# Sensing.net
KiCad netlist of a schematic drawn in EAGLE
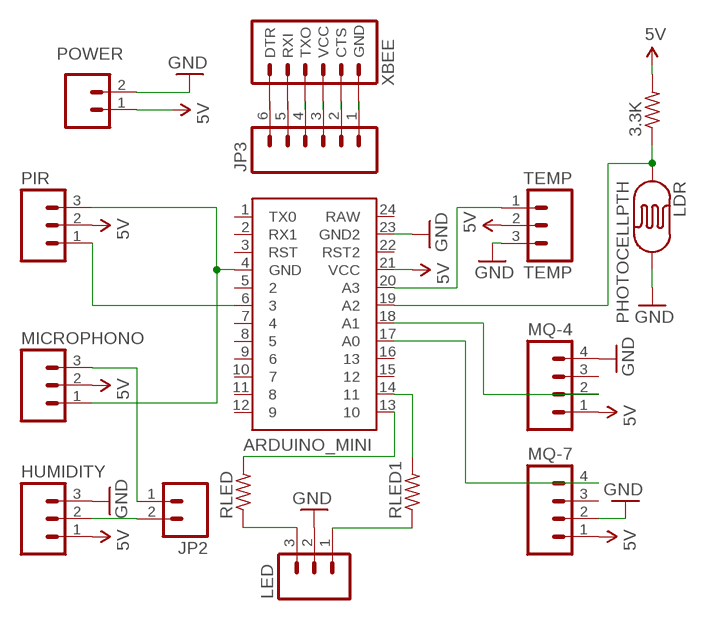
[diagram p0: schematic, sheet 1]

(export (version "E")
  (design (tool "Eeschema 10.0.6"))
  (components
    (comp (ref "3.3K")
      (value "R-US_M0805")
      (footprint "eagle-import:M0805")
      (libsource (lib "eagle-import") (part "R-US_M0805"))
    )
    (comp (ref "ARDUINO_MINI")
      (value "ARDUINO_MINI")
      (footprint "eagle-import:ARDUINO_MINI")
      (libsource (lib "eagle-import") (part "ARDUINO_MINI"))
    )
    (comp (ref "HUMIDITY")
      (value "HUMIDITY")
      (footprint "eagle-import:1X03")
      (libsource (lib "eagle-import") (part "M03PTH"))
    )
    (comp (ref "JP2")
      (value "M02PTH")
      (footprint "eagle-import:1X02")
      (libsource (lib "eagle-import") (part "M02PTH"))
    )
    (comp (ref "JP3")
      (value "M06SIP")
      (footprint "eagle-import:1X06")
      (libsource (lib "eagle-import") (part "M06SIP"))
    )
    (comp (ref "LDR")
      (value "PHOTOCELLPTH")
      (footprint "eagle-import:PHOTOCELL")
      (libsource (lib "eagle-import") (part "PHOTOCELLPTH"))
    )
    (comp (ref "LED")
      (value "M03PTH")
      (footprint "eagle-import:1X03")
      (libsource (lib "eagle-import") (part "M03PTH"))
    )
    (comp (ref "MICROPHONO")
      (value "M03PTH")
      (footprint "eagle-import:1X03")
      (libsource (lib "eagle-import") (part "M03PTH"))
    )
    (comp (ref "MQ-4")
      (value "M04PTH")
      (footprint "eagle-import:1X04")
      (libsource (lib "eagle-import") (part "M04PTH"))
    )
    (comp (ref "MQ-7")
      (value "M04PTH")
      (footprint "eagle-import:1X04")
      (libsource (lib "eagle-import") (part "M04PTH"))
    )
    (comp (ref "PIR")
      (value "M03PTH")
      (footprint "eagle-import:1X03")
      (libsource (lib "eagle-import") (part "M03PTH"))
    )
    (comp (ref "POWER")
      (value "M025MM")
      (footprint "eagle-import:SCREWTERMINAL-5MM-2")
      (libsource (lib "eagle-import") (part "M025MM"))
    )
    (comp (ref "RLED")
      (value "R-US_M0805")
      (footprint "eagle-import:M0805")
      (libsource (lib "eagle-import") (part "R-US_M0805"))
    )
    (comp (ref "RLED1")
      (value "R-US_M0805")
      (footprint "eagle-import:M0805")
      (libsource (lib "eagle-import") (part "R-US_M0805"))
    )
    (comp (ref "TEMP")
      (value "TEMP")
      (footprint "eagle-import:1X03_NO_SILK")
      (libsource (lib "eagle-import") (part "M031X03_NO_SILK"))
    )
    (comp (ref "XBEE")
      (value "ARDUINO_SERIAL_PROGRAMPTH")
      (footprint "eagle-import:1X06")
      (libsource (lib "eagle-import") (part "ARDUINO_SERIAL_PROGRAMPTH"))
    )
  )
  (nets
    (net (code "1") (name "5V") (class "Default")
      (node (ref "3.3K") (pin "2") (pinfunction "2_2") (pintype "passive"))
      (node (ref "ARDUINO_MINI") (pin "21") (pinfunction "VCC_21") (pintype "bidirectional"))
      (node (ref "HUMIDITY") (pin "1") (pinfunction "1_1") (pintype "passive"))
      (node (ref "MICROPHONO") (pin "2") (pinfunction "2_2") (pintype "passive"))
      (node (ref "MQ-4") (pin "1") (pinfunction "1_1") (pintype "passive"))
      (node (ref "MQ-7") (pin "1") (pinfunction "1_1") (pintype "passive"))
      (node (ref "PIR") (pin "2") (pinfunction "2_2") (pintype "passive"))
      (node (ref "POWER") (pin "1") (pinfunction "1_1") (pintype "passive"))
      (node (ref "TEMP") (pin "2") (pinfunction "2_2") (pintype "passive"))
    )
    (net (code "2") (name "GND") (class "Default")
      (node (ref "ARDUINO_MINI") (pin "23") (pinfunction "GND2_23") (pintype "bidirectional"))
      (node (ref "HUMIDITY") (pin "3") (pinfunction "3_3") (pintype "passive"))
      (node (ref "LDR") (pin "2") (pinfunction "P$2_2") (pintype "bidirectional"))
      (node (ref "LED") (pin "2") (pinfunction "2_2") (pintype "passive"))
      (node (ref "MQ-4") (pin "4") (pinfunction "4_4") (pintype "passive"))
      (node (ref "MQ-7") (pin "2") (pinfunction "2_2") (pintype "passive"))
      (node (ref "POWER") (pin "2") (pinfunction "2_2") (pintype "passive"))
      (node (ref "TEMP") (pin "3") (pinfunction "3_3") (pintype "passive"))
    )
    (net (code "3") (name "Net-(ARDUINO_MINI-3)") (class "Default")
      (node (ref "ARDUINO_MINI") (pin "6") (pinfunction "3_6") (pintype "bidirectional"))
      (node (ref "PIR") (pin "1") (pinfunction "1_1") (pintype "passive"))
    )
    (net (code "4") (name "Net-(ARDUINO_MINI-10)") (class "Default")
      (node (ref "ARDUINO_MINI") (pin "13") (pinfunction "10_13") (pintype "bidirectional"))
      (node (ref "RLED") (pin "2") (pinfunction "2_2") (pintype "passive"))
    )
    (net (code "5") (name "Net-(ARDUINO_MINI-11)") (class "Default")
      (node (ref "ARDUINO_MINI") (pin "14") (pinfunction "11_14") (pintype "bidirectional"))
      (node (ref "RLED1") (pin "2") (pinfunction "2_2") (pintype "passive"))
    )
    (net (code "6") (name "Net-(ARDUINO_MINI-A0)") (class "Default")
      (node (ref "ARDUINO_MINI") (pin "17") (pinfunction "A0_17") (pintype "bidirectional"))
      (node (ref "MQ-7") (pin "4") (pinfunction "4_4") (pintype "passive"))
    )
    (net (code "7") (name "Net-(ARDUINO_MINI-A1)") (class "Default")
      (node (ref "ARDUINO_MINI") (pin "18") (pinfunction "A1_18") (pintype "bidirectional"))
      (node (ref "MQ-4") (pin "2") (pinfunction "2_2") (pintype "passive"))
    )
    (net (code "8") (name "Net-(ARDUINO_MINI-A2)") (class "Default")
      (node (ref "3.3K") (pin "1") (pinfunction "1_1") (pintype "passive"))
      (node (ref "ARDUINO_MINI") (pin "19") (pinfunction "A2_19") (pintype "bidirectional"))
      (node (ref "LDR") (pin "1") (pinfunction "P$1_1") (pintype "bidirectional"))
    )
    (net (code "9") (name "Net-(ARDUINO_MINI-A3)") (class "Default")
      (node (ref "ARDUINO_MINI") (pin "20") (pinfunction "A3_20") (pintype "bidirectional"))
      (node (ref "TEMP") (pin "1") (pinfunction "1_1") (pintype "passive"))
    )
    (net (code "10") (name "Net-(ARDUINO_MINI-GND)") (class "Default")
      (node (ref "ARDUINO_MINI") (pin "4") (pinfunction "GND_4") (pintype "bidirectional"))
      (node (ref "MICROPHONO") (pin "1") (pinfunction "1_1") (pintype "passive"))
      (node (ref "PIR") (pin "3") (pinfunction "3_3") (pintype "passive"))
    )
    (net (code "11") (name "Net-(HUMIDITY-Pad2)") (class "Default")
      (node (ref "HUMIDITY") (pin "2") (pinfunction "2_2") (pintype "passive"))
      (node (ref "JP2") (pin "2") (pinfunction "2_2") (pintype "passive"))
    )
    (net (code "12") (name "Net-(JP2-Pad1)") (class "Default")
      (node (ref "JP2") (pin "1") (pinfunction "1_1") (pintype "passive"))
      (node (ref "MICROPHONO") (pin "3") (pinfunction "3_3") (pintype "passive"))
    )
    (net (code "13") (name "Net-(LED-Pad1)") (class "Default")
      (node (ref "LED") (pin "1") (pinfunction "1_1") (pintype "passive"))
      (node (ref "RLED1") (pin "1") (pinfunction "1_1") (pintype "passive"))
    )
    (net (code "14") (name "Net-(LED-Pad3)") (class "Default")
      (node (ref "LED") (pin "3") (pinfunction "3_3") (pintype "passive"))
      (node (ref "RLED") (pin "1") (pinfunction "1_1") (pintype "passive"))
    )
    (net (code "15") (name "Net-(XBEE-CTS)") (class "Default")
      (node (ref "JP3") (pin "2") (pinfunction "2_2") (pintype "passive"))
      (node (ref "XBEE") (pin "5") (pinfunction "CTS_5") (pintype "passive"))
    )
    (net (code "16") (name "Net-(XBEE-DTR)") (class "Default")
      (node (ref "JP3") (pin "6") (pinfunction "6_6") (pintype "passive"))
      (node (ref "XBEE") (pin "1") (pinfunction "DTR_1") (pintype "passive"))
    )
    (net (code "17") (name "Net-(XBEE-GND)") (class "Default")
      (node (ref "JP3") (pin "1") (pinfunction "1_1") (pintype "passive"))
      (node (ref "XBEE") (pin "6") (pinfunction "GND_6") (pintype "passive"))
    )
    (net (code "18") (name "Net-(XBEE-RXI)") (class "Default")
      (node (ref "JP3") (pin "5") (pinfunction "5_5") (pintype "passive"))
      (node (ref "XBEE") (pin "2") (pinfunction "RXI_2") (pintype "passive"))
    )
    (net (code "19") (name "Net-(XBEE-TXO)") (class "Default")
      (node (ref "JP3") (pin "4") (pinfunction "4_4") (pintype "passive"))
      (node (ref "XBEE") (pin "3") (pinfunction "TXO_3") (pintype "passive"))
    )
    (net (code "20") (name "Net-(XBEE-VCC)") (class "Default")
      (node (ref "JP3") (pin "3") (pinfunction "3_3") (pintype "passive"))
      (node (ref "XBEE") (pin "4") (pinfunction "VCC_4") (pintype "passive"))
    )
    (net (code "21") (name "unconnected-(ARDUINO_MINI-2-Pad5)") (class "Default")
      (node (ref "ARDUINO_MINI") (pin "5") (pinfunction "2_5") (pintype "bidirectional"))
    )
    (net (code "22") (name "unconnected-(ARDUINO_MINI-4-Pad7)") (class "Default")
      (node (ref "ARDUINO_MINI") (pin "7") (pinfunction "4_7") (pintype "bidirectional"))
    )
    (net (code "23") (name "unconnected-(ARDUINO_MINI-5-Pad8)") (class "Default")
      (node (ref "ARDUINO_MINI") (pin "8") (pinfunction "5_8") (pintype "bidirectional"))
    )
    (net (code "24") (name "unconnected-(ARDUINO_MINI-6-Pad9)") (class "Default")
      (node (ref "ARDUINO_MINI") (pin "9") (pinfunction "6_9") (pintype "bidirectional"))
    )
    (net (code "25") (name "unconnected-(ARDUINO_MINI-7-Pad10)") (class "Default")
      (node (ref "ARDUINO_MINI") (pin "10") (pinfunction "7_10") (pintype "bidirectional"))
    )
    (net (code "26") (name "unconnected-(ARDUINO_MINI-8-Pad11)") (class "Default")
      (node (ref "ARDUINO_MINI") (pin "11") (pinfunction "8_11") (pintype "bidirectional"))
    )
    (net (code "27") (name "unconnected-(ARDUINO_MINI-9-Pad12)") (class "Default")
      (node (ref "ARDUINO_MINI") (pin "12") (pinfunction "9_12") (pintype "bidirectional"))
    )
    (net (code "28") (name "unconnected-(ARDUINO_MINI-12-Pad15)") (class "Default")
      (node (ref "ARDUINO_MINI") (pin "15") (pinfunction "12_15") (pintype "bidirectional"))
    )
    (net (code "29") (name "unconnected-(ARDUINO_MINI-13-Pad16)") (class "Default")
      (node (ref "ARDUINO_MINI") (pin "16") (pinfunction "13_16") (pintype "bidirectional"))
    )
    (net (code "30") (name "unconnected-(ARDUINO_MINI-RAW-Pad24)") (class "Default")
      (node (ref "ARDUINO_MINI") (pin "24") (pinfunction "RAW_24") (pintype "bidirectional"))
    )
    (net (code "31") (name "unconnected-(ARDUINO_MINI-RST-Pad3)") (class "Default")
      (node (ref "ARDUINO_MINI") (pin "3") (pinfunction "RST_3") (pintype "bidirectional"))
    )
    (net (code "32") (name "unconnected-(ARDUINO_MINI-RST2-Pad22)") (class "Default")
      (node (ref "ARDUINO_MINI") (pin "22") (pinfunction "RST2_22") (pintype "bidirectional"))
    )
    (net (code "33") (name "unconnected-(ARDUINO_MINI-RX1-Pad2)") (class "Default")
      (node (ref "ARDUINO_MINI") (pin "2") (pinfunction "RX1_2") (pintype "bidirectional"))
    )
    (net (code "34") (name "unconnected-(ARDUINO_MINI-TX0-Pad1)") (class "Default")
      (node (ref "ARDUINO_MINI") (pin "1") (pinfunction "TX0_1") (pintype "bidirectional"))
    )
    (net (code "35") (name "unconnected-(MQ-4-Pad3)") (class "Default")
      (node (ref "MQ-4") (pin "3") (pinfunction "3_3") (pintype "passive"))
    )
    (net (code "36") (name "unconnected-(MQ-7-Pad3)") (class "Default")
      (node (ref "MQ-7") (pin "3") (pinfunction "3_3") (pintype "passive"))
    )
  )
)
